# Adafruit_PiTFT_Plus_3_5in.net
KiCad netlist of a schematic drawn in EAGLE
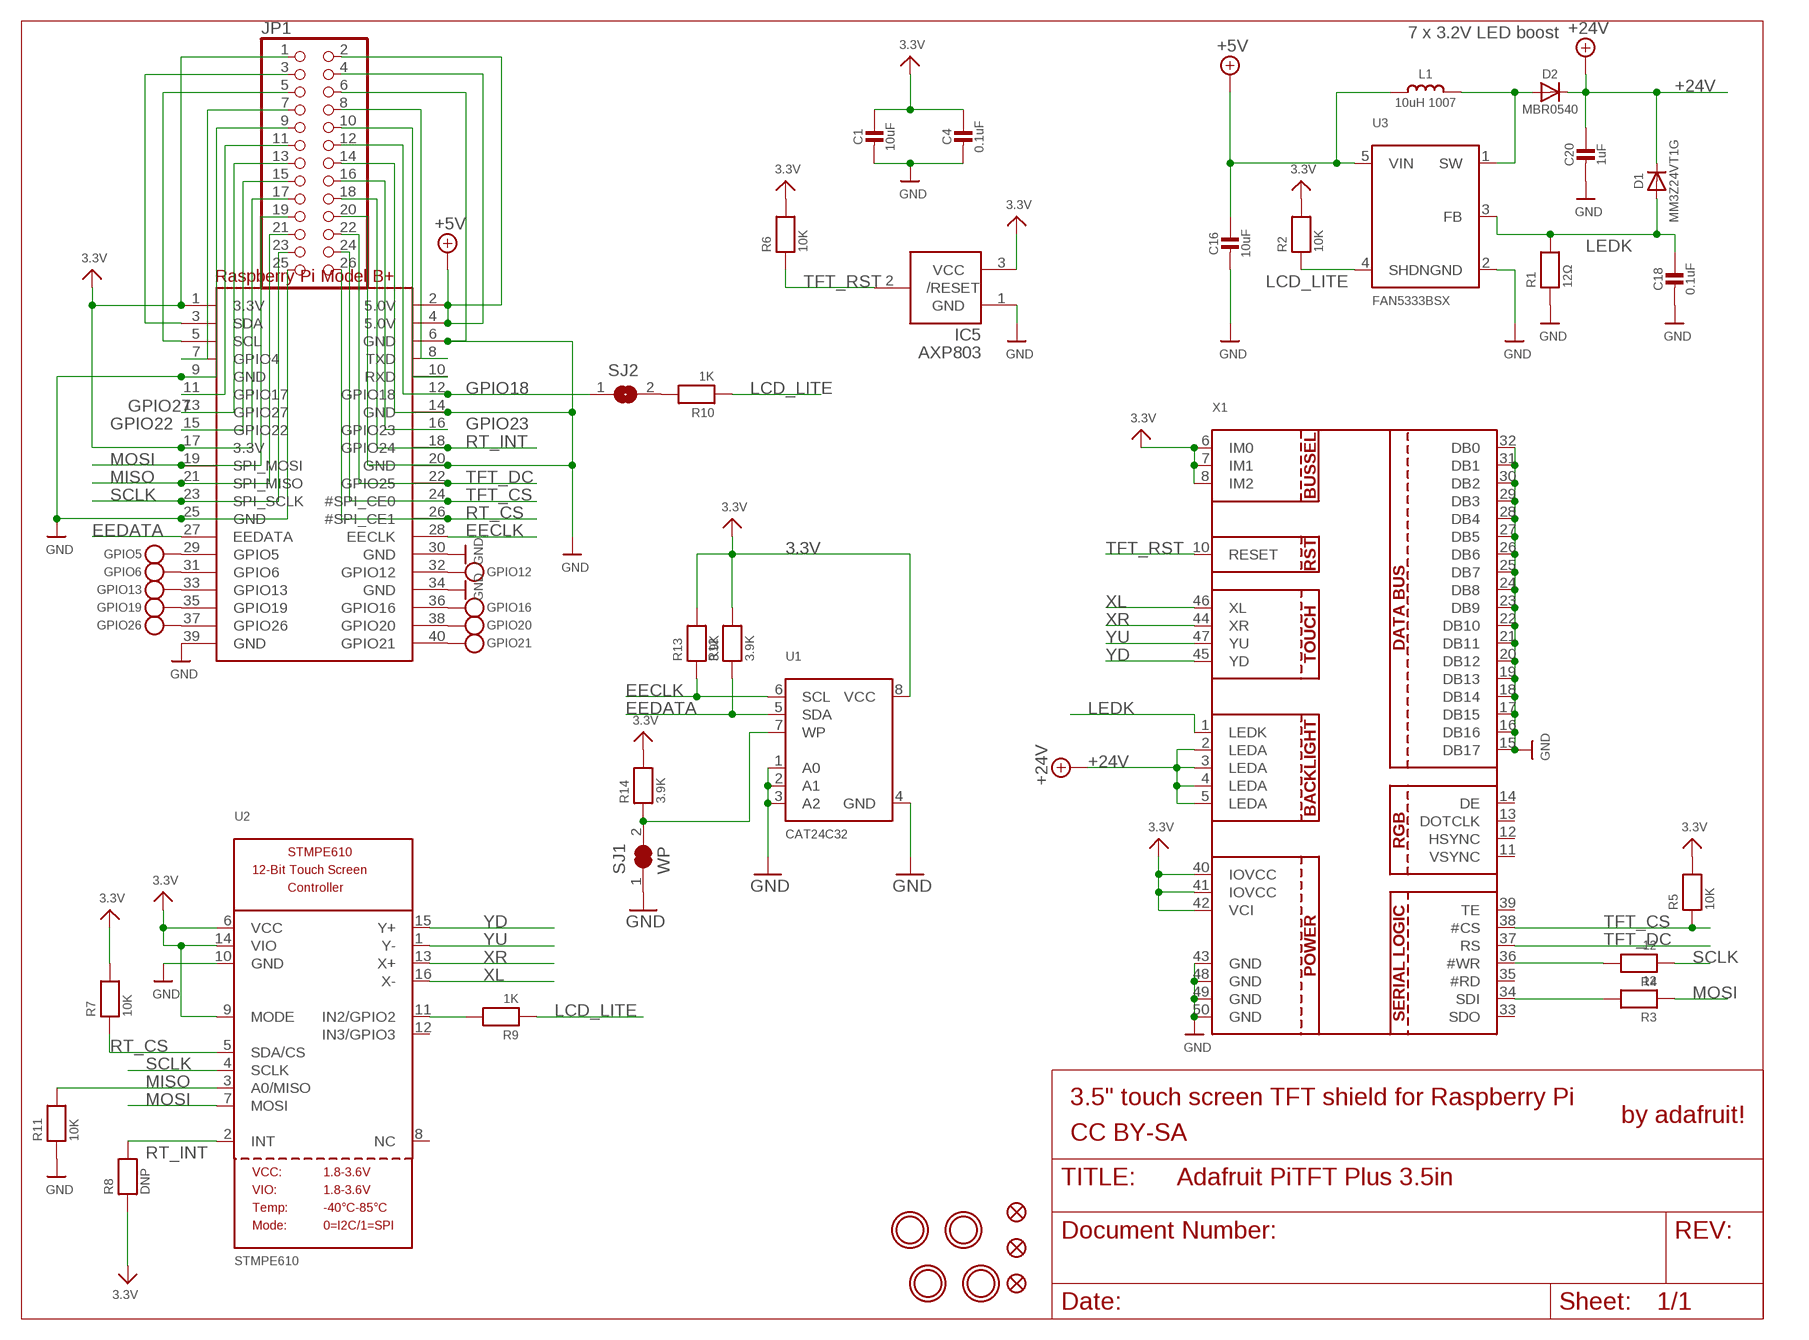
[diagram p0: schematic, sheet 1]

(export (version "E")
  (design (tool "Eeschema 10.0.6"))
  (components
    (comp (ref "C1")
      (value "10uF")
      (footprint "eagle-import:0805-NO")
      (libsource (lib "eagle-import") (part "CAP_CERAMIC0805-NOOUTLINE"))
    )
    (comp (ref "C4")
      (value "0.1uF")
      (footprint "eagle-import:0805-NO")
      (libsource (lib "eagle-import") (part "CAP_CERAMIC0805-NOOUTLINE"))
    )
    (comp (ref "C16")
      (value "10uF")
      (footprint "eagle-import:0805-NO")
      (libsource (lib "eagle-import") (part "CAP_CERAMIC0805-NOOUTLINE"))
    )
    (comp (ref "C18")
      (value "0.1uF")
      (footprint "eagle-import:0805-NO")
      (libsource (lib "eagle-import") (part "CAP_CERAMIC0805-NOOUTLINE"))
    )
    (comp (ref "C20")
      (value "1uF")
      (footprint "eagle-import:_0805MP")
      (libsource (lib "eagle-import") (part "CAP_CERAMIC_0805MP"))
    )
    (comp (ref "D1")
      (value "MM3Z24VT1G")
      (footprint "eagle-import:SMADIODE")
      (libsource (lib "eagle-import") (part "DIODESMA"))
    )
    (comp (ref "D2")
      (value "MBR0540")
      (footprint "eagle-import:SOD-123")
      (libsource (lib "eagle-import") (part "DIODESOD-123"))
    )
    (comp (ref "GPIO5")
      (value "TESTPOINT1.5X2.0MM_NOCREAM")
      (footprint "eagle-import:PAD-1.5X2.0")
      (libsource (lib "eagle-import") (part "TESTPOINT1.5X2.0MM_NOCREAM"))
    )
    (comp (ref "GPIO6")
      (value "TESTPOINT1.5X2.0MM_NOCREAM")
      (footprint "eagle-import:PAD-1.5X2.0")
      (libsource (lib "eagle-import") (part "TESTPOINT1.5X2.0MM_NOCREAM"))
    )
    (comp (ref "GPIO12")
      (value "TESTPOINT1.5X2.0MM_NOCREAM")
      (footprint "eagle-import:PAD-1.5X2.0")
      (libsource (lib "eagle-import") (part "TESTPOINT1.5X2.0MM_NOCREAM"))
    )
    (comp (ref "GPIO13")
      (value "TESTPOINT1.5X2.0MM_NOCREAM")
      (footprint "eagle-import:PAD-1.5X2.0")
      (libsource (lib "eagle-import") (part "TESTPOINT1.5X2.0MM_NOCREAM"))
    )
    (comp (ref "GPIO16")
      (value "TESTPOINT1.5X2.0MM_NOCREAM")
      (footprint "eagle-import:PAD-1.5X2.0")
      (libsource (lib "eagle-import") (part "TESTPOINT1.5X2.0MM_NOCREAM"))
    )
    (comp (ref "GPIO19")
      (value "TESTPOINT1.5X2.0MM_NOCREAM")
      (footprint "eagle-import:PAD-1.5X2.0")
      (libsource (lib "eagle-import") (part "TESTPOINT1.5X2.0MM_NOCREAM"))
    )
    (comp (ref "GPIO20")
      (value "TESTPOINT1.5X2.0MM_NOCREAM")
      (footprint "eagle-import:PAD-1.5X2.0")
      (libsource (lib "eagle-import") (part "TESTPOINT1.5X2.0MM_NOCREAM"))
    )
    (comp (ref "GPIO21")
      (value "TESTPOINT1.5X2.0MM_NOCREAM")
      (footprint "eagle-import:PAD-1.5X2.0")
      (libsource (lib "eagle-import") (part "TESTPOINT1.5X2.0MM_NOCREAM"))
    )
    (comp (ref "GPIO26")
      (value "TESTPOINT1.5X2.0MM_NOCREAM")
      (footprint "eagle-import:PAD-1.5X2.0")
      (libsource (lib "eagle-import") (part "TESTPOINT1.5X2.0MM_NOCREAM"))
    )
    (comp (ref "IC5")
      (value "AXP803")
      (footprint "eagle-import:SOT23")
      (libsource (lib "eagle-import") (part "AXP083-SAG"))
    )
    (comp (ref "JP1")
      (value "HEADER-2X13-SMT")
      (footprint "eagle-import:2X13_SMT_MALE")
      (libsource (lib "eagle-import") (part "HEADER-2X13-SMT"))
    )
    (comp (ref "L1")
      (value "10uH 1007")
      (footprint "eagle-import:INDUCTOR_1007")
      (libsource (lib "eagle-import") (part "INDUCTOR"))
    )
    (comp (ref "R1")
      (value "12Ω")
      (footprint "eagle-import:0805-NO")
      (libsource (lib "eagle-import") (part "RESISTOR0805_NOOUTLINE"))
    )
    (comp (ref "R2")
      (value "10K")
      (footprint "eagle-import:0805-NO")
      (libsource (lib "eagle-import") (part "RESISTOR0805_NOOUTLINE"))
    )
    (comp (ref "R3")
      (value "12")
      (footprint "eagle-import:_0805MP")
      (libsource (lib "eagle-import") (part "RESISTOR_0805MP"))
    )
    (comp (ref "R4")
      (value "12")
      (footprint "eagle-import:0805-NO")
      (libsource (lib "eagle-import") (part "RESISTOR0805_NOOUTLINE"))
    )
    (comp (ref "R5")
      (value "10K")
      (footprint "eagle-import:0805-NO")
      (libsource (lib "eagle-import") (part "RESISTOR0805_NOOUTLINE"))
    )
    (comp (ref "R6")
      (value "10K")
      (footprint "eagle-import:0805-NO")
      (libsource (lib "eagle-import") (part "RESISTOR0805_NOOUTLINE"))
    )
    (comp (ref "R7")
      (value "10K")
      (footprint "eagle-import:0805-NO")
      (libsource (lib "eagle-import") (part "RESISTOR0805_NOOUTLINE"))
    )
    (comp (ref "R8")
      (value "DNP")
      (footprint "eagle-import:0805-NO")
      (libsource (lib "eagle-import") (part "RESISTOR0805_NOOUTLINE"))
    )
    (comp (ref "R9")
      (value "1K")
      (footprint "eagle-import:_0805MP")
      (libsource (lib "eagle-import") (part "RESISTOR_0805MP"))
    )
    (comp (ref "R10")
      (value "1K")
      (footprint "eagle-import:0805-NO")
      (libsource (lib "eagle-import") (part "RESISTOR0805_NOOUTLINE"))
    )
    (comp (ref "R11")
      (value "10K")
      (footprint "eagle-import:0805-NO")
      (libsource (lib "eagle-import") (part "RESISTOR0805_NOOUTLINE"))
    )
    (comp (ref "R12")
      (value "3.9K")
      (footprint "eagle-import:0805-NO")
      (libsource (lib "eagle-import") (part "RESISTOR0805_NOOUTLINE"))
    )
    (comp (ref "R13")
      (value "3.9K")
      (footprint "eagle-import:0805-NO")
      (libsource (lib "eagle-import") (part "RESISTOR0805_NOOUTLINE"))
    )
    (comp (ref "R14")
      (value "3.9K")
      (footprint "eagle-import:0805-NO")
      (libsource (lib "eagle-import") (part "RESISTOR0805_NOOUTLINE"))
    )
    (comp (ref "RPI1")
      (value "RASPBERRYPI_BPLUS_SMT")
      (footprint "eagle-import:RASPBERRYPI_BPLUS_SHIELD_SMT")
      (libsource (lib "eagle-import") (part "RASPBERRYPI_BPLUS_SMT"))
    )
    (comp (ref "SJ1")
      (value "WP")
      (footprint "eagle-import:SOLDERJUMPER_CLOSEDWIRE")
      (libsource (lib "eagle-import") (part "SOLDERJUMPER_CLOSED"))
    )
    (comp (ref "SJ2")
      (value "SOLDERJUMPERCLOSED")
      (footprint "eagle-import:SOLDERJUMPER_CLOSEDWIRE")
      (libsource (lib "eagle-import") (part "SOLDERJUMPERCLOSED"))
    )
    (comp (ref "U$10")
      (value "FIDUCIAL\"\"")
      (footprint "eagle-import:FIDUCIAL_1MM")
      (libsource (lib "eagle-import") (part "FIDUCIAL{dblquote}{dblquote}"))
    )
    (comp (ref "U$11")
      (value "FIDUCIAL\"\"")
      (footprint "eagle-import:FIDUCIAL_1MM")
      (libsource (lib "eagle-import") (part "FIDUCIAL{dblquote}{dblquote}"))
    )
    (comp (ref "U$15")
      (value "MOUNTINGHOLE2.5_THICK")
      (footprint "eagle-import:MOUNTINGHOLE_2.5_PLATED_THICK")
      (libsource (lib "eagle-import") (part "MOUNTINGHOLE2.5_THICK"))
    )
    (comp (ref "U$16")
      (value "MOUNTINGHOLE2.5_THICK")
      (footprint "eagle-import:MOUNTINGHOLE_2.5_PLATED_THICK")
      (libsource (lib "eagle-import") (part "MOUNTINGHOLE2.5_THICK"))
    )
    (comp (ref "U$17")
      (value "MOUNTINGHOLE2.5_THICK")
      (footprint "eagle-import:MOUNTINGHOLE_2.5_PLATED_THICK")
      (fields (field (name "BOM") "EXCLUDE"))
      (libsource (lib "eagle-import") (part "MOUNTINGHOLE2.5_THICK"))
    )
    (comp (ref "U$18")
      (value "FIDUCIAL\"\"")
      (footprint "eagle-import:FIDUCIAL_1MM")
      (libsource (lib "eagle-import") (part "FIDUCIAL{dblquote}{dblquote}"))
    )
    (comp (ref "U$20")
      (value "MOUNTINGHOLE2.5_THICK")
      (footprint "eagle-import:MOUNTINGHOLE_2.5_PLATED_THICK")
      (fields (field (name "BOM") "EXCLUDE"))
      (libsource (lib "eagle-import") (part "MOUNTINGHOLE2.5_THICK"))
    )
    (comp (ref "U1")
      (value "CAT24C32")
      (footprint "eagle-import:SOIC8_150MIL")
      (libsource (lib "eagle-import") (part "EEPROM_I2C_SOIC8_GENERIC"))
    )
    (comp (ref "U2")
      (value "STMPE610")
      (footprint "eagle-import:QFN16_3MM")
      (libsource (lib "eagle-import") (part "STMPE610"))
    )
    (comp (ref "U3")
      (value "FAN5333BSX")
      (footprint "eagle-import:SOT23-5@1")
      (libsource (lib "eagle-import") (part "FAN5331"))
    )
    (comp (ref "X1")
      (value "DISP_LCD_3.5IN_320X480_50PIN")
      (footprint "eagle-import:TFT_3.5IN_320X480_50PIN")
      (libsource (lib "eagle-import") (part "DISP_LCD_3.5IN_320X480_50PIN"))
    )
  )
  (nets
    (net (code "1") (name "+5V") (class "Default")
      (node (ref "C16") (pin "1") (pinfunction "1_1") (pintype "passive"))
      (node (ref "JP1") (pin "2") (pinfunction "2_2") (pintype "passive"))
      (node (ref "JP1") (pin "4") (pinfunction "4_4") (pintype "passive"))
      (node (ref "L1") (pin "P$1") (pinfunction "1_P$1") (pintype "passive"))
      (node (ref "RPI1") (pin "2") (pinfunction "5.0V_2") (pintype "power_in"))
      (node (ref "RPI1") (pin "4") (pinfunction "5.0V_4") (pintype "power_in"))
      (node (ref "U3") (pin "5") (pinfunction "VIN_5") (pintype "bidirectional"))
    )
    (net (code "2") (name "+24V") (class "Default")
      (node (ref "C20") (pin "1") (pinfunction "1_1") (pintype "passive"))
      (node (ref "D1") (pin "C") (pinfunction "C_C") (pintype "passive"))
      (node (ref "D2") (pin "C") (pinfunction "C_C") (pintype "passive"))
      (node (ref "X1") (pin "2") (pinfunction "LEDA_2") (pintype "bidirectional"))
      (node (ref "X1") (pin "3") (pinfunction "LEDA_3") (pintype "bidirectional"))
      (node (ref "X1") (pin "4") (pinfunction "LEDA_4") (pintype "bidirectional"))
      (node (ref "X1") (pin "5") (pinfunction "LEDA_5") (pintype "bidirectional"))
    )
    (net (code "3") (name "/EECLK") (class "Default")
      (node (ref "R13") (pin "1") (pinfunction "1_1") (pintype "passive"))
      (node (ref "RPI1") (pin "28") (pinfunction "EECLK_28") (pintype "power_in"))
      (node (ref "U1") (pin "6") (pinfunction "SCL_6") (pintype "input"))
    )
    (net (code "4") (name "/EEDATA") (class "Default")
      (node (ref "R12") (pin "1") (pinfunction "1_1") (pintype "passive"))
      (node (ref "RPI1") (pin "27") (pinfunction "EEDATA_27") (pintype "bidirectional"))
      (node (ref "U1") (pin "5") (pinfunction "SDA_5") (pintype "bidirectional"))
    )
    (net (code "5") (name "/GPIO18") (class "Default")
      (node (ref "JP1") (pin "12") (pinfunction "12_12") (pintype "passive"))
      (node (ref "RPI1") (pin "12") (pinfunction "GPIO18_12") (pintype "bidirectional"))
      (node (ref "SJ2") (pin "1") (pinfunction "1_1") (pintype "passive"))
    )
    (net (code "6") (name "/GPIO22") (class "Default")
      (node (ref "JP1") (pin "15") (pinfunction "15_15") (pintype "passive"))
      (node (ref "RPI1") (pin "15") (pinfunction "GPIO22_15") (pintype "bidirectional"))
    )
    (net (code "7") (name "/GPIO23") (class "Default")
      (node (ref "JP1") (pin "16") (pinfunction "16_16") (pintype "passive"))
      (node (ref "RPI1") (pin "16") (pinfunction "GPIO23_16") (pintype "bidirectional"))
    )
    (net (code "8") (name "/GPIO27") (class "Default")
      (node (ref "JP1") (pin "13") (pinfunction "13_13") (pintype "passive"))
      (node (ref "RPI1") (pin "13") (pinfunction "GPIO27_13") (pintype "bidirectional"))
    )
    (net (code "9") (name "/LCD_LITE") (class "Default")
      (node (ref "R10") (pin "1") (pinfunction "1_1") (pintype "passive"))
      (node (ref "R2") (pin "1") (pinfunction "1_1") (pintype "passive"))
      (node (ref "R9") (pin "1") (pinfunction "1_1") (pintype "passive"))
      (node (ref "U3") (pin "4") (pinfunction "SHDN_4") (pintype "bidirectional"))
    )
    (net (code "10") (name "/LEDK") (class "Default")
      (node (ref "C18") (pin "1") (pinfunction "1_1") (pintype "passive"))
      (node (ref "D1") (pin "A") (pinfunction "A_A") (pintype "passive"))
      (node (ref "R1") (pin "2") (pinfunction "2_2") (pintype "passive"))
      (node (ref "U3") (pin "3") (pinfunction "FB_3") (pintype "bidirectional"))
      (node (ref "X1") (pin "1") (pinfunction "LEDK_1") (pintype "bidirectional"))
    )
    (net (code "11") (name "/MISO") (class "Default")
      (node (ref "JP1") (pin "21") (pinfunction "21_21") (pintype "passive"))
      (node (ref "R11") (pin "2") (pinfunction "2_2") (pintype "passive"))
      (node (ref "RPI1") (pin "21") (pinfunction "SPI_MISO_21") (pintype "bidirectional"))
      (node (ref "U2") (pin "3") (pinfunction "A0/MISO_3") (pintype "bidirectional"))
    )
    (net (code "12") (name "/MOSI") (class "Default")
      (node (ref "JP1") (pin "19") (pinfunction "19_19") (pintype "passive"))
      (node (ref "R3") (pin "1") (pinfunction "1_1") (pintype "passive"))
      (node (ref "RPI1") (pin "19") (pinfunction "SPI_MOSI_19") (pintype "bidirectional"))
      (node (ref "U2") (pin "7") (pinfunction "MOSI_7") (pintype "input"))
    )
    (net (code "13") (name "/RT_CS") (class "Default")
      (node (ref "JP1") (pin "26") (pinfunction "26_26") (pintype "passive"))
      (node (ref "R7") (pin "1") (pinfunction "1_1") (pintype "passive"))
      (node (ref "RPI1") (pin "26") (pinfunction "#SPI_CE1_26") (pintype "bidirectional"))
      (node (ref "U2") (pin "5") (pinfunction "SDA/CS_5") (pintype "bidirectional"))
    )
    (net (code "14") (name "/RT_INT") (class "Default")
      (node (ref "JP1") (pin "18") (pinfunction "18_18") (pintype "passive"))
      (node (ref "R8") (pin "2") (pinfunction "2_2") (pintype "passive"))
      (node (ref "RPI1") (pin "18") (pinfunction "GPIO24_18") (pintype "bidirectional"))
      (node (ref "U2") (pin "2") (pinfunction "INT_2") (pintype "output"))
    )
    (net (code "15") (name "/SCLK") (class "Default")
      (node (ref "JP1") (pin "23") (pinfunction "23_23") (pintype "passive"))
      (node (ref "R4") (pin "1") (pinfunction "1_1") (pintype "passive"))
      (node (ref "RPI1") (pin "23") (pinfunction "SPI_SCLK_23") (pintype "bidirectional"))
      (node (ref "U2") (pin "4") (pinfunction "SCLK_4") (pintype "bidirectional"))
    )
    (net (code "16") (name "/TFT_CS") (class "Default")
      (node (ref "JP1") (pin "24") (pinfunction "24_24") (pintype "passive"))
      (node (ref "R5") (pin "1") (pinfunction "1_1") (pintype "passive"))
      (node (ref "RPI1") (pin "24") (pinfunction "#SPI_CE0_24") (pintype "bidirectional"))
      (node (ref "X1") (pin "38") (pinfunction "#CS_38") (pintype "bidirectional"))
    )
    (net (code "17") (name "/TFT_DC") (class "Default")
      (node (ref "JP1") (pin "22") (pinfunction "22_22") (pintype "passive"))
      (node (ref "RPI1") (pin "22") (pinfunction "GPIO25_22") (pintype "bidirectional"))
      (node (ref "X1") (pin "37") (pinfunction "RS_37") (pintype "bidirectional"))
    )
    (net (code "18") (name "/TFT_RST") (class "Default")
      (node (ref "IC5") (pin "2") (pinfunction "/RESET_2") (pintype "output"))
      (node (ref "R6") (pin "1") (pinfunction "1_1") (pintype "passive"))
      (node (ref "X1") (pin "10") (pinfunction "RESET_10") (pintype "bidirectional"))
    )
    (net (code "19") (name "/XL") (class "Default")
      (node (ref "U2") (pin "16") (pinfunction "X-_16") (pintype "input"))
      (node (ref "X1") (pin "46") (pinfunction "XL_46") (pintype "bidirectional"))
    )
    (net (code "20") (name "/XR") (class "Default")
      (node (ref "U2") (pin "13") (pinfunction "X+_13") (pintype "input"))
      (node (ref "X1") (pin "44") (pinfunction "XR_44") (pintype "bidirectional"))
    )
    (net (code "21") (name "/YD") (class "Default")
      (node (ref "U2") (pin "15") (pinfunction "Y+_15") (pintype "input"))
      (node (ref "X1") (pin "45") (pinfunction "YD_45") (pintype "bidirectional"))
    )
    (net (code "22") (name "/YU") (class "Default")
      (node (ref "U2") (pin "1") (pinfunction "Y-_1") (pintype "input"))
      (node (ref "X1") (pin "47") (pinfunction "YU_47") (pintype "bidirectional"))
    )
    (net (code "23") (name "3.3V") (class "Default")
      (node (ref "C1") (pin "1") (pinfunction "1_1") (pintype "passive"))
      (node (ref "C4") (pin "1") (pinfunction "1_1") (pintype "passive"))
      (node (ref "IC5") (pin "3") (pinfunction "VCC_3") (pintype "power_in"))
      (node (ref "JP1") (pin "1") (pinfunction "1_1") (pintype "passive"))
      (node (ref "JP1") (pin "17") (pinfunction "17_17") (pintype "passive"))
      (node (ref "R12") (pin "2") (pinfunction "2_2") (pintype "passive"))
      (node (ref "R13") (pin "2") (pinfunction "2_2") (pintype "passive"))
      (node (ref "R14") (pin "2") (pinfunction "2_2") (pintype "passive"))
      (node (ref "R2") (pin "2") (pinfunction "2_2") (pintype "passive"))
      (node (ref "R5") (pin "2") (pinfunction "2_2") (pintype "passive"))
      (node (ref "R6") (pin "2") (pinfunction "2_2") (pintype "passive"))
      (node (ref "R7") (pin "2") (pinfunction "2_2") (pintype "passive"))
      (node (ref "R8") (pin "1") (pinfunction "1_1") (pintype "passive"))
      (node (ref "RPI1") (pin "1") (pinfunction "3.3V_1") (pintype "power_in"))
      (node (ref "RPI1") (pin "17") (pinfunction "3.3V_17") (pintype "power_in"))
      (node (ref "U1") (pin "8") (pinfunction "VCC_8") (pintype "power_in"))
      (node (ref "U2") (pin "14") (pinfunction "VIO_14") (pintype "power_in"))
      (node (ref "U2") (pin "6") (pinfunction "VCC_6") (pintype "power_in"))
      (node (ref "U2") (pin "9") (pinfunction "MODE_9") (pintype "input"))
      (node (ref "X1") (pin "40") (pinfunction "IOVCC_40") (pintype "bidirectional"))
      (node (ref "X1") (pin "41") (pinfunction "IOVCC_41") (pintype "bidirectional"))
      (node (ref "X1") (pin "42") (pinfunction "VCI_42") (pintype "bidirectional"))
      (node (ref "X1") (pin "6") (pinfunction "IM0_6") (pintype "bidirectional"))
      (node (ref "X1") (pin "7") (pinfunction "IM1_7") (pintype "bidirectional"))
      (node (ref "X1") (pin "8") (pinfunction "IM2_8") (pintype "bidirectional"))
    )
    (net (code "24") (name "GND") (class "Default")
      (node (ref "C1") (pin "2") (pinfunction "2_2") (pintype "passive"))
      (node (ref "C16") (pin "2") (pinfunction "2_2") (pintype "passive"))
      (node (ref "C18") (pin "2") (pinfunction "2_2") (pintype "passive"))
      (node (ref "C20") (pin "2") (pinfunction "2_2") (pintype "passive"))
      (node (ref "C4") (pin "2") (pinfunction "2_2") (pintype "passive"))
      (node (ref "IC5") (pin "1") (pinfunction "GND_1") (pintype "power_in"))
      (node (ref "JP1") (pin "14") (pinfunction "14_14") (pintype "passive"))
      (node (ref "JP1") (pin "20") (pinfunction "20_20") (pintype "passive"))
      (node (ref "JP1") (pin "25") (pinfunction "25_25") (pintype "passive"))
      (node (ref "JP1") (pin "6") (pinfunction "6_6") (pintype "passive"))
      (node (ref "JP1") (pin "9") (pinfunction "9_9") (pintype "passive"))
      (node (ref "R1") (pin "1") (pinfunction "1_1") (pintype "passive"))
      (node (ref "R11") (pin "1") (pinfunction "1_1") (pintype "passive"))
      (node (ref "RPI1") (pin "14") (pinfunction "GND_14") (pintype "power_in"))
      (node (ref "RPI1") (pin "20") (pinfunction "GND_20") (pintype "power_in"))
      (node (ref "RPI1") (pin "25") (pinfunction "GND_25") (pintype "power_in"))
      (node (ref "RPI1") (pin "30") (pinfunction "GND_30") (pintype "bidirectional"))
      (node (ref "RPI1") (pin "34") (pinfunction "GND_34") (pintype "bidirectional"))
      (node (ref "RPI1") (pin "39") (pinfunction "GND_39") (pintype "power_in"))
      (node (ref "RPI1") (pin "6") (pinfunction "GND_6") (pintype "power_in"))
      (node (ref "RPI1") (pin "9") (pinfunction "GND_9") (pintype "power_in"))
      (node (ref "SJ1") (pin "1") (pinfunction "1_1") (pintype "passive"))
      (node (ref "U1") (pin "1") (pinfunction "A0_1") (pintype "input"))
      (node (ref "U1") (pin "2") (pinfunction "A1_2") (pintype "input"))
      (node (ref "U1") (pin "3") (pinfunction "A2_3") (pintype "input"))
      (node (ref "U1") (pin "4") (pinfunction "GND_4") (pintype "power_in"))
      (node (ref "U2") (pin "10") (pinfunction "GND_10") (pintype "power_in"))
      (node (ref "U3") (pin "2") (pinfunction "GND_2") (pintype "bidirectional"))
      (node (ref "X1") (pin "15") (pinfunction "DB17_15") (pintype "bidirectional"))
      (node (ref "X1") (pin "16") (pinfunction "DB16_16") (pintype "bidirectional"))
      (node (ref "X1") (pin "17") (pinfunction "DB15_17") (pintype "bidirectional"))
      (node (ref "X1") (pin "18") (pinfunction "DB14_18") (pintype "bidirectional"))
      (node (ref "X1") (pin "19") (pinfunction "DB13_19") (pintype "bidirectional"))
      (node (ref "X1") (pin "20") (pinfunction "DB12_20") (pintype "bidirectional"))
      (node (ref "X1") (pin "21") (pinfunction "DB11_21") (pintype "bidirectional"))
      (node (ref "X1") (pin "22") (pinfunction "DB10_22") (pintype "bidirectional"))
      (node (ref "X1") (pin "23") (pinfunction "DB9_23") (pintype "bidirectional"))
      (node (ref "X1") (pin "24") (pinfunction "DB8_24") (pintype "bidirectional"))
      (node (ref "X1") (pin "25") (pinfunction "DB7_25") (pintype "bidirectional"))
      (node (ref "X1") (pin "26") (pinfunction "DB6_26") (pintype "bidirectional"))
      (node (ref "X1") (pin "27") (pinfunction "DB5_27") (pintype "bidirectional"))
      (node (ref "X1") (pin "28") (pinfunction "DB4_28") (pintype "bidirectional"))
      (node (ref "X1") (pin "29") (pinfunction "DB3_29") (pintype "bidirectional"))
      (node (ref "X1") (pin "30") (pinfunction "DB2_30") (pintype "bidirectional"))
      (node (ref "X1") (pin "31") (pinfunction "DB1_31") (pintype "bidirectional"))
      (node (ref "X1") (pin "32") (pinfunction "DB0_32") (pintype "bidirectional"))
      (node (ref "X1") (pin "43") (pinfunction "GND_43") (pintype "bidirectional"))
      (node (ref "X1") (pin "48") (pinfunction "GND_48") (pintype "bidirectional"))
      (node (ref "X1") (pin "49") (pinfunction "GND_49") (pintype "bidirectional"))
      (node (ref "X1") (pin "50") (pinfunction "GND_50") (pintype "bidirectional"))
    )
    (net (code "25") (name "Net-(L1-2)") (class "Default")
      (node (ref "D2") (pin "A") (pinfunction "A_A") (pintype "passive"))
      (node (ref "L1") (pin "P$2") (pinfunction "2_P$2") (pintype "passive"))
      (node (ref "U3") (pin "1") (pinfunction "SW_1") (pintype "bidirectional"))
    )
    (net (code "26") (name "Net-(R10-Pad2)") (class "Default")
      (node (ref "R10") (pin "2") (pinfunction "2_2") (pintype "passive"))
      (node (ref "SJ2") (pin "2") (pinfunction "2_2") (pintype "passive"))
    )
    (net (code "27") (name "Net-(RPI1-GPIO4)") (class "Default")
      (node (ref "JP1") (pin "7") (pinfunction "7_7") (pintype "passive"))
      (node (ref "RPI1") (pin "7") (pinfunction "GPIO4_7") (pintype "bidirectional"))
    )
    (net (code "28") (name "Net-(RPI1-GPIO5)") (class "Default")
      (node (ref "GPIO5") (pin "P$1") (pinfunction "P$1_P$1") (pintype "bidirectional"))
      (node (ref "RPI1") (pin "29") (pinfunction "GPIO5_29") (pintype "bidirectional"))
    )
    (net (code "29") (name "Net-(RPI1-GPIO6)") (class "Default")
      (node (ref "GPIO6") (pin "P$1") (pinfunction "P$1_P$1") (pintype "bidirectional"))
      (node (ref "RPI1") (pin "31") (pinfunction "GPIO6_31") (pintype "power_in"))
    )
    (net (code "30") (name "Net-(RPI1-GPIO12)") (class "Default")
      (node (ref "GPIO12") (pin "P$1") (pinfunction "P$1_P$1") (pintype "bidirectional"))
      (node (ref "RPI1") (pin "32") (pinfunction "GPIO12_32") (pintype "bidirectional"))
    )
    (net (code "31") (name "Net-(RPI1-GPIO13)") (class "Default")
      (node (ref "GPIO13") (pin "P$1") (pinfunction "P$1_P$1") (pintype "bidirectional"))
      (node (ref "RPI1") (pin "33") (pinfunction "GPIO13_33") (pintype "bidirectional"))
    )
    (net (code "32") (name "Net-(RPI1-GPIO16)") (class "Default")
      (node (ref "GPIO16") (pin "P$1") (pinfunction "P$1_P$1") (pintype "bidirectional"))
      (node (ref "RPI1") (pin "36") (pinfunction "GPIO16_36") (pintype "power_in"))
    )
    (net (code "33") (name "Net-(RPI1-GPIO17)") (class "Default")
      (node (ref "JP1") (pin "11") (pinfunction "11_11") (pintype "passive"))
      (node (ref "RPI1") (pin "11") (pinfunction "GPIO17_11") (pintype "bidirectional"))
    )
    (net (code "34") (name "Net-(RPI1-GPIO19)") (class "Default")
      (node (ref "GPIO19") (pin "P$1") (pinfunction "P$1_P$1") (pintype "bidirectional"))
      (node (ref "RPI1") (pin "35") (pinfunction "GPIO19_35") (pintype "bidirectional"))
    )
    (net (code "35") (name "Net-(RPI1-GPIO20)") (class "Default")
      (node (ref "GPIO20") (pin "P$1") (pinfunction "P$1_P$1") (pintype "bidirectional"))
      (node (ref "RPI1") (pin "38") (pinfunction "GPIO20_38") (pintype "bidirectional"))
    )
    (net (code "36") (name "Net-(RPI1-GPIO21)") (class "Default")
      (node (ref "GPIO21") (pin "P$1") (pinfunction "P$1_P$1") (pintype "bidirectional"))
      (node (ref "RPI1") (pin "40") (pinfunction "GPIO21_40") (pintype "bidirectional"))
    )
    (net (code "37") (name "Net-(RPI1-GPIO26)") (class "Default")
      (node (ref "GPIO26") (pin "P$1") (pinfunction "P$1_P$1") (pintype "bidirectional"))
      (node (ref "RPI1") (pin "37") (pinfunction "GPIO26_37") (pintype "bidirectional"))
    )
    (net (code "38") (name "Net-(RPI1-RXD)") (class "Default")
      (node (ref "JP1") (pin "10") (pinfunction "10_10") (pintype "passive"))
      (node (ref "RPI1") (pin "10") (pinfunction "RXD_10") (pintype "bidirectional"))
    )
    (net (code "39") (name "Net-(RPI1-SCL)") (class "Default")
      (node (ref "JP1") (pin "5") (pinfunction "5_5") (pintype "passive"))
      (node (ref "RPI1") (pin "5") (pinfunction "SCL_5") (pintype "bidirectional"))
    )
    (net (code "40") (name "Net-(RPI1-SDA)") (class "Default")
      (node (ref "JP1") (pin "3") (pinfunction "3_3") (pintype "passive"))
      (node (ref "RPI1") (pin "3") (pinfunction "SDA_3") (pintype "bidirectional"))
    )
    (net (code "41") (name "Net-(RPI1-TXD)") (class "Default")
      (node (ref "JP1") (pin "8") (pinfunction "8_8") (pintype "passive"))
      (node (ref "RPI1") (pin "8") (pinfunction "TXD_8") (pintype "output"))
    )
    (net (code "42") (name "Net-(U1-WP)") (class "Default")
      (node (ref "R14") (pin "1") (pinfunction "1_1") (pintype "passive"))
      (node (ref "SJ1") (pin "2") (pinfunction "2_2") (pintype "passive"))
      (node (ref "U1") (pin "7") (pinfunction "WP_7") (pintype "input"))
    )
    (net (code "43") (name "Net-(U2-IN2{slash}GPIO2)") (class "Default")
      (node (ref "R9") (pin "2") (pinfunction "2_2") (pintype "passive"))
      (node (ref "U2") (pin "11") (pinfunction "IN2/GPIO2_11") (pintype "bidirectional"))
    )
    (net (code "44") (name "Net-(X1-#WR)") (class "Default")
      (node (ref "R4") (pin "2") (pinfunction "2_2") (pintype "passive"))
      (node (ref "X1") (pin "36") (pinfunction "#WR_36") (pintype "bidirectional"))
    )
    (net (code "45") (name "Net-(X1-SDI)") (class "Default")
      (node (ref "R3") (pin "2") (pinfunction "2_2") (pintype "passive"))
      (node (ref "X1") (pin "34") (pinfunction "SDI_34") (pintype "bidirectional"))
    )
    (net (code "46") (name "unconnected-(U2-IN3{slash}GPIO3-Pad12)") (class "Default")
      (node (ref "U2") (pin "12") (pinfunction "IN3/GPIO3_12") (pintype "bidirectional"))
    )
    (net (code "47") (name "unconnected-(U2-NC-Pad8)") (class "Default")
      (node (ref "U2") (pin "8") (pinfunction "NC_8") (pintype "no_connect"))
    )
    (net (code "48") (name "unconnected-(X1-#RD-Pad35)") (class "Default")
      (node (ref "X1") (pin "35") (pinfunction "#RD_35") (pintype "bidirectional"))
    )
    (net (code "49") (name "unconnected-(X1-DE-Pad14)") (class "Default")
      (node (ref "X1") (pin "14") (pinfunction "DE_14") (pintype "bidirectional"))
    )
    (net (code "50") (name "unconnected-(X1-DOTCLK-Pad13)") (class "Default")
      (node (ref "X1") (pin "13") (pinfunction "DOTCLK_13") (pintype "bidirectional"))
    )
    (net (code "51") (name "unconnected-(X1-HSYNC-Pad12)") (class "Default")
      (node (ref "X1") (pin "12") (pinfunction "HSYNC_12") (pintype "bidirectional"))
    )
    (net (code "52") (name "unconnected-(X1-SDO-Pad33)") (class "Default")
      (node (ref "X1") (pin "33") (pinfunction "SDO_33") (pintype "bidirectional"))
    )
    (net (code "53") (name "unconnected-(X1-TE-Pad39)") (class "Default")
      (node (ref "X1") (pin "39") (pinfunction "TE_39") (pintype "bidirectional"))
    )
    (net (code "54") (name "unconnected-(X1-VSYNC-Pad11)") (class "Default")
      (node (ref "X1") (pin "11") (pinfunction "VSYNC_11") (pintype "bidirectional"))
    )
  )
)
